# HDMI8x8_OutputConnector.net
KiCad netlist of a schematic drawn in Altium Designer
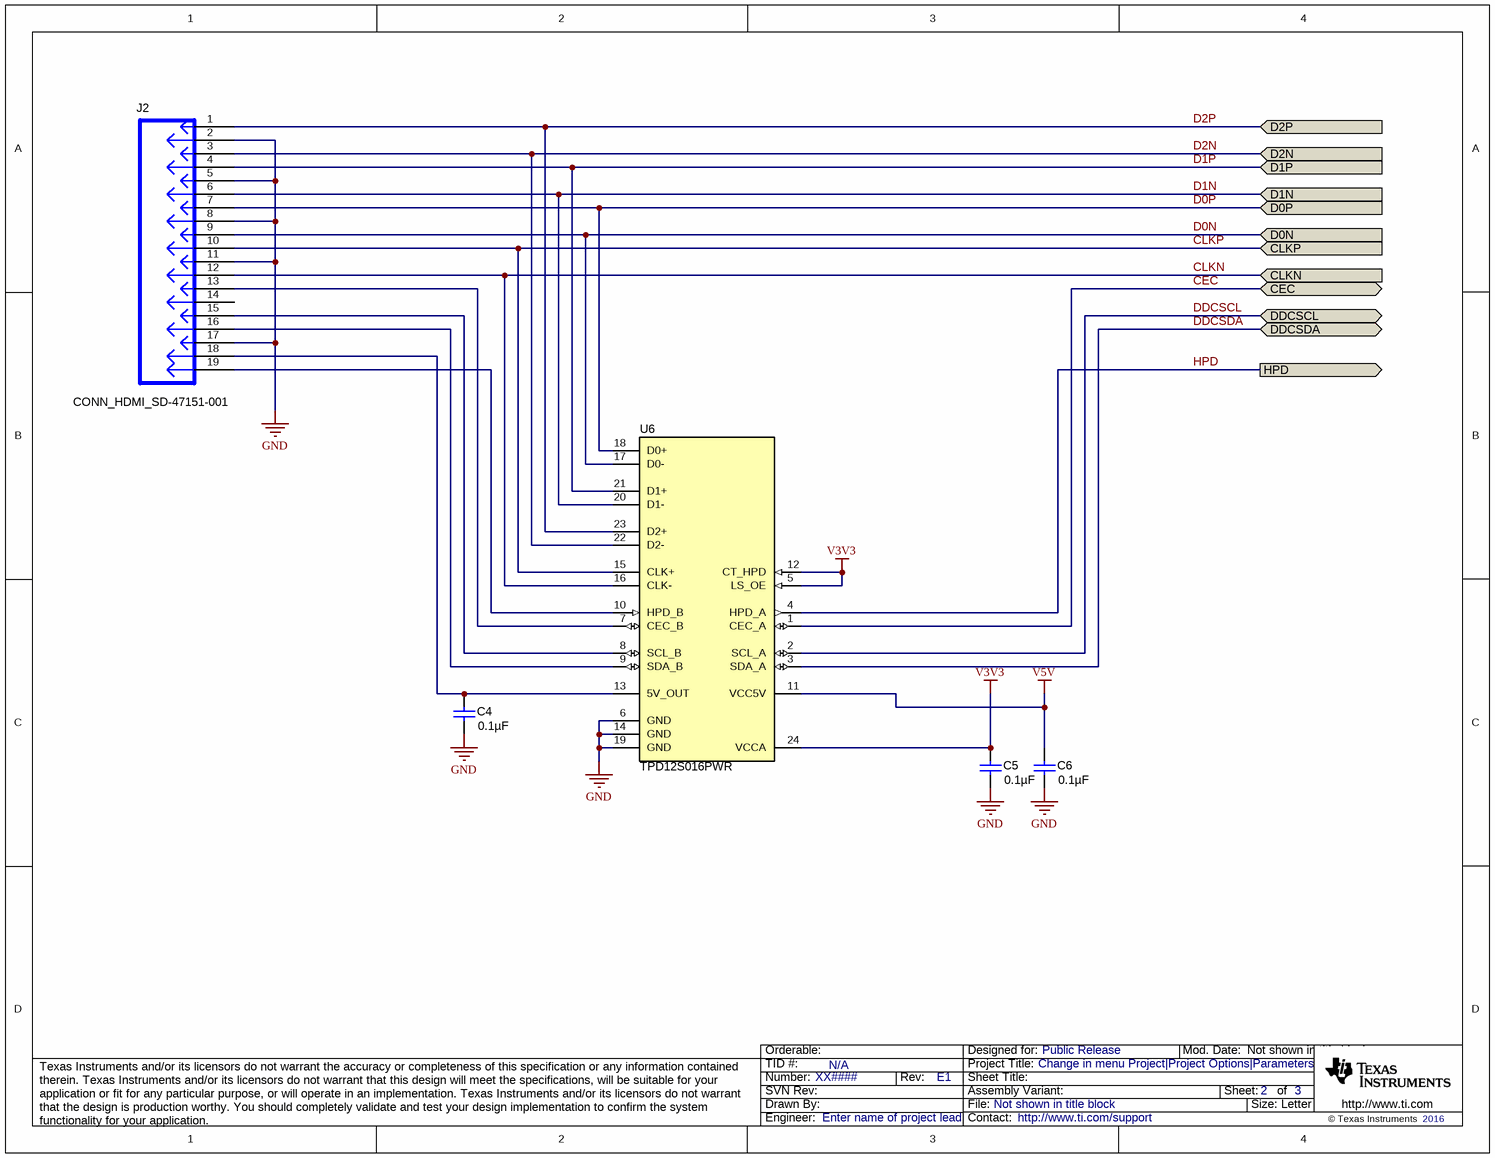
[diagram p0: HDMI8x8_OutputConnector.SchDoc]

(export (version "E")
  (design (tool "Eeschema 10.0.6"))
  (components
    (comp (ref "C4")
      (value "C0603C104M4RACTU")
      (footprint "0603")
      (description "CAP, CERM, 0.1 µF, 16 V, +/- 20%, X7R, 0603")
      (fields
        (field (name "VALUEDISPLAYED") "0.1µF")
        (field (name "MANUFACTURER") "Kemet")
        (field (name "PUBLISHER") "Texas Instruments")
      )
      (libsource (lib "Capacitor_Ceramic") (part "C0603C104M4RACTU"))
    )
    (comp (ref "C5")
      (value "C0603C104M4RACTU")
      (footprint "0603")
      (description "CAP, CERM, 0.1 µF, 16 V, +/- 20%, X7R, 0603")
      (fields
        (field (name "VALUEDISPLAYED") "0.1µF")
        (field (name "MANUFACTURER") "Kemet")
        (field (name "PUBLISHER") "Texas Instruments")
      )
      (libsource (lib "Capacitor_Ceramic") (part "C0603C104M4RACTU"))
    )
    (comp (ref "C6")
      (value "C0603C104M4RACTU")
      (footprint "0603")
      (description "CAP, CERM, 0.1 µF, 16 V, +/- 20%, X7R, 0603")
      (fields
        (field (name "VALUEDISPLAYED") "0.1µF")
        (field (name "MANUFACTURER") "Kemet")
        (field (name "PUBLISHER") "Texas Instruments")
      )
      (libsource (lib "Capacitor_Ceramic") (part "C0603C104M4RACTU"))
    )
    (comp (ref "J2")
      (value "CONN_HDMI_SD-47151-001")
      (footprint "CONN_HDMI_SD-47151")
      (description "Connector, HDMI, RA, 19 pin")
      (fields (field (name "MANUFACTURER") "Molex") (field (name "PARTNUMBER") "SD-47151-0001"))
      (libsource (lib "PADSlegacy_Hardware") (part "CONN_HDMI_SD-47151-001"))
    )
    (comp (ref "U6")
      (value "TPD12S016PWR")
      (footprint "PW0024A_N")
      (fields
        (field (name "MANUFACTURER") "Texas Instruments")
        (field (name "ALTERNATE PARTNUMBER") "Equivalent")
      )
      (libsource (lib "TI Interface ESD EMI Protection") (part "TPD12S016PWR"))
    )
  )
  (nets
    (net (code "1") (name "/CEC") (class "Default")
      (node (ref "U6") (pin "1") (pinfunction "CEC_A_1") (pintype "bidirectional"))
    )
    (net (code "2") (name "/CLKN") (class "Default")
      (node (ref "J2") (pin "12") (pintype "passive"))
      (node (ref "U6") (pin "16") (pinfunction "CLK-_16") (pintype "passive"))
    )
    (net (code "3") (name "/CLKP") (class "Default")
      (node (ref "J2") (pin "10") (pintype "passive"))
      (node (ref "U6") (pin "15") (pinfunction "CLK+_15") (pintype "passive"))
    )
    (net (code "4") (name "/D0N") (class "Default")
      (node (ref "J2") (pin "9") (pintype "passive"))
      (node (ref "U6") (pin "17") (pinfunction "D0-_17") (pintype "passive"))
    )
    (net (code "5") (name "/D0P") (class "Default")
      (node (ref "J2") (pin "7") (pintype "passive"))
      (node (ref "U6") (pin "18") (pinfunction "D0+_18") (pintype "passive"))
    )
    (net (code "6") (name "/D1N") (class "Default")
      (node (ref "J2") (pin "6") (pintype "passive"))
      (node (ref "U6") (pin "20") (pinfunction "D1-_20") (pintype "passive"))
    )
    (net (code "7") (name "/D1P") (class "Default")
      (node (ref "J2") (pin "4") (pintype "passive"))
      (node (ref "U6") (pin "21") (pinfunction "D1+_21") (pintype "passive"))
    )
    (net (code "8") (name "/D2N") (class "Default")
      (node (ref "J2") (pin "3") (pintype "passive"))
      (node (ref "U6") (pin "22") (pinfunction "D2-_22") (pintype "passive"))
    )
    (net (code "9") (name "/D2P") (class "Default")
      (node (ref "J2") (pin "1") (pintype "passive"))
      (node (ref "U6") (pin "23") (pinfunction "D2+_23") (pintype "passive"))
    )
    (net (code "10") (name "/DDCSCL") (class "Default")
      (node (ref "U6") (pin "2") (pinfunction "SCL_A_2") (pintype "bidirectional"))
    )
    (net (code "11") (name "/DDCSDA") (class "Default")
      (node (ref "U6") (pin "3") (pinfunction "SDA_A_3") (pintype "bidirectional"))
    )
    (net (code "12") (name "/HPD") (class "Default")
      (node (ref "U6") (pin "4") (pinfunction "HPD_A_4") (pintype "output"))
    )
    (net (code "13") (name "GND") (class "Default")
      (node (ref "C4") (pin "2") (pinfunction "2_2") (pintype "passive"))
      (node (ref "C5") (pin "2") (pinfunction "2_2") (pintype "passive"))
      (node (ref "C6") (pin "2") (pinfunction "2_2") (pintype "passive"))
      (node (ref "J2") (pin "11") (pintype "passive"))
      (node (ref "J2") (pin "17") (pintype "passive"))
      (node (ref "J2") (pin "2") (pintype "passive"))
      (node (ref "J2") (pin "5") (pintype "passive"))
      (node (ref "J2") (pin "8") (pintype "passive"))
      (node (ref "U6") (pin "14") (pinfunction "GND_14") (pintype "power_in"))
      (node (ref "U6") (pin "19") (pinfunction "GND_19") (pintype "power_in"))
      (node (ref "U6") (pin "6") (pinfunction "GND_6") (pintype "power_in"))
    )
    (net (code "14") (name "Net-(U6-5V_OUT)") (class "Default")
      (node (ref "C4") (pin "1") (pinfunction "1_1") (pintype "passive"))
      (node (ref "J2") (pin "18") (pintype "passive"))
      (node (ref "U6") (pin "13") (pinfunction "5V_OUT_13") (pintype "power_in"))
    )
    (net (code "15") (name "Net-(U6-CEC_B)") (class "Default")
      (node (ref "J2") (pin "13") (pintype "passive"))
      (node (ref "U6") (pin "7") (pinfunction "CEC_B_7") (pintype "bidirectional"))
    )
    (net (code "16") (name "Net-(U6-HPD_B)") (class "Default")
      (node (ref "J2") (pin "19") (pintype "passive"))
      (node (ref "U6") (pin "10") (pinfunction "HPD_B_10") (pintype "input"))
    )
    (net (code "17") (name "Net-(U6-SCL_B)") (class "Default")
      (node (ref "J2") (pin "15") (pintype "passive"))
      (node (ref "U6") (pin "8") (pinfunction "SCL_B_8") (pintype "bidirectional"))
    )
    (net (code "18") (name "Net-(U6-SDA_B)") (class "Default")
      (node (ref "J2") (pin "16") (pintype "passive"))
      (node (ref "U6") (pin "9") (pinfunction "SDA_B_9") (pintype "bidirectional"))
    )
    (net (code "19") (name "V3V3") (class "Default")
      (node (ref "C5") (pin "1") (pinfunction "1_1") (pintype "passive"))
      (node (ref "U6") (pin "12") (pinfunction "CT_HPD_12") (pintype "input"))
      (node (ref "U6") (pin "24") (pinfunction "VCCA_24") (pintype "power_in"))
      (node (ref "U6") (pin "5") (pinfunction "LS_OE_5") (pintype "input"))
    )
    (net (code "20") (name "V5V") (class "Default")
      (node (ref "C6") (pin "1") (pinfunction "1_1") (pintype "passive"))
      (node (ref "U6") (pin "11") (pinfunction "VCC5V_11") (pintype "power_in"))
    )
    (net (code "21") (name "unconnected-(J2-Pad14)") (class "Default")
      (node (ref "J2") (pin "14") (pintype "passive"))
    )
  )
)
